# fpga_config.net
KiCad netlist of a schematic drawn in Altium Designer
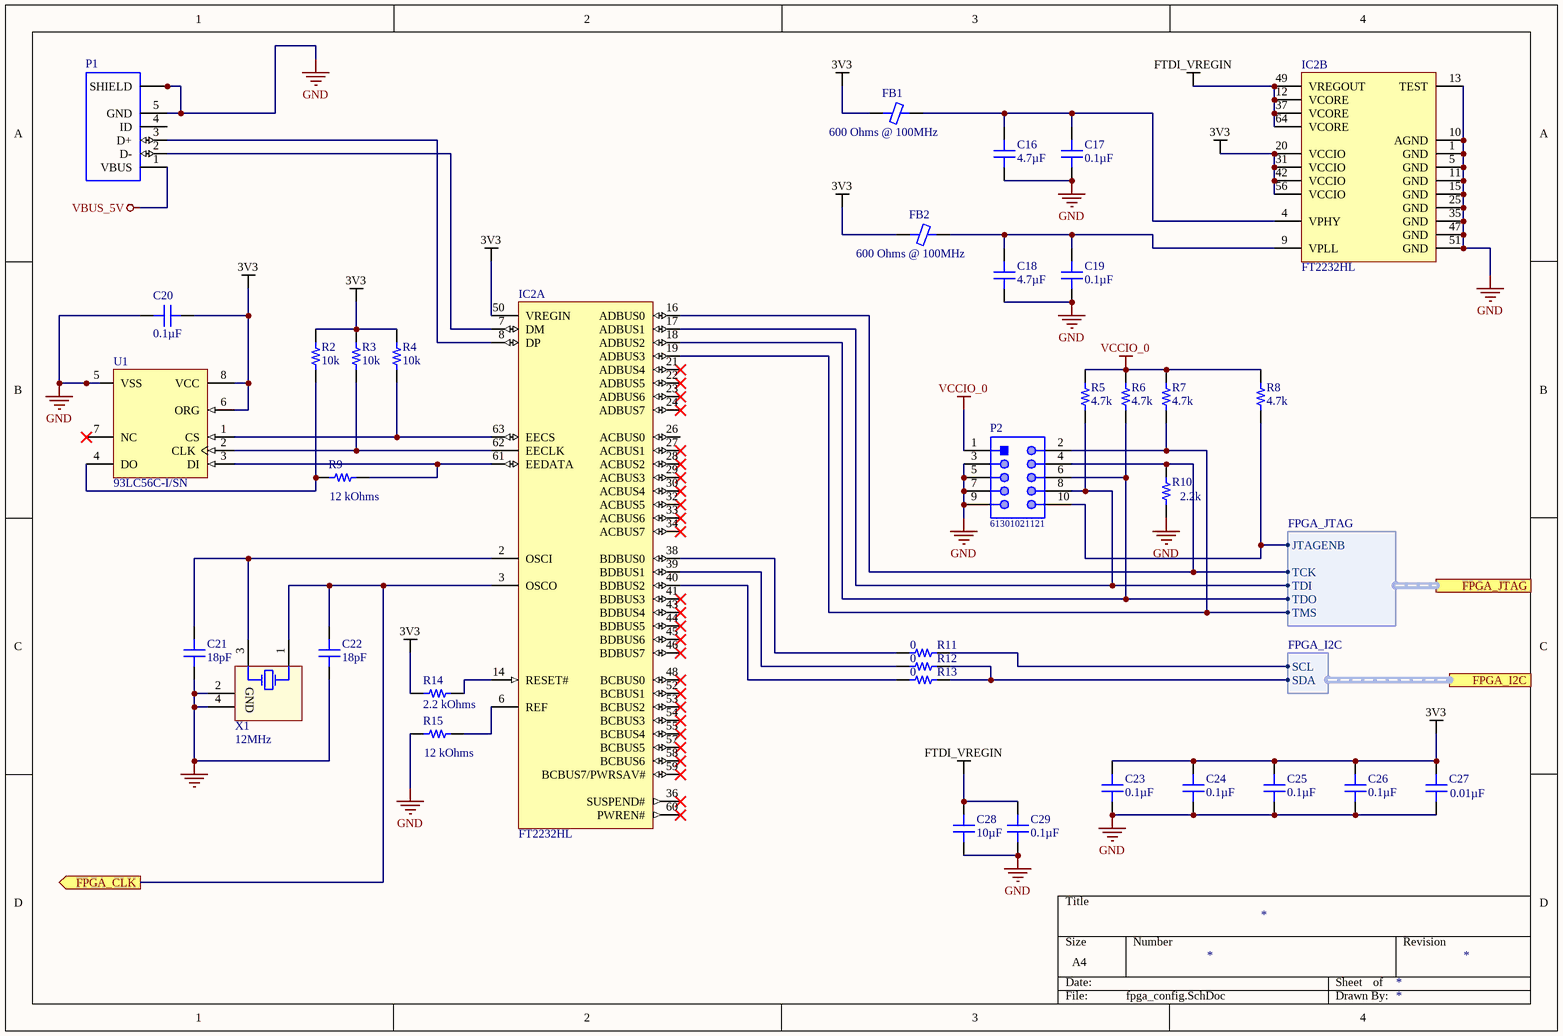
[diagram p0: fpga_config.SchDoc]

(export (version "E")
  (design (tool "Eeschema 10.0.6"))
  (components
    (comp (ref "C16")
      (value "4.7µF")
      (footprint "CAP 0603_1608")
      (description "CAP CER 4.7UF 10V X5R 0603")
      (fields (field (name "PART NUMBER") "LMK107BJ475KA-T") (field (name "MANUFACTURER") "Taiyo Yuden"))
      (libsource (lib "Celestial Altium Library - altium_library (2)") (part "Capacitor"))
    )
    (comp (ref "C17")
      (value "0.1µF")
      (footprint "CAP 0603_1608")
      (description "CAP CER 0.1UF 50V X7R 0603")
      (fields (field (name "PART NUMBER") "C0603C104K5RAC7411") (field (name "MANUFACTURER") "KEMET"))
      (libsource (lib "Celestial Altium Library - altium_library (2)") (part "Capacitor"))
    )
    (comp (ref "C18")
      (value "4.7µF")
      (footprint "CAP 0603_1608")
      (description "CAP CER 4.7UF 10V X5R 0603")
      (fields (field (name "PART NUMBER") "LMK107BJ475KA-T") (field (name "MANUFACTURER") "Taiyo Yuden"))
      (libsource (lib "Celestial Altium Library - altium_library (2)") (part "Capacitor"))
    )
    (comp (ref "C19")
      (value "0.1µF")
      (footprint "CAP 0603_1608")
      (description "CAP CER 0.1UF 50V X7R 0603")
      (fields (field (name "PART NUMBER") "C0603C104K5RAC7411") (field (name "MANUFACTURER") "KEMET"))
      (libsource (lib "Celestial Altium Library - altium_library (2)") (part "Capacitor"))
    )
    (comp (ref "C20")
      (value "0.1µF")
      (footprint "CAP 0603_1608")
      (description "CAP CER 0.1UF 50V X7R 0603")
      (fields (field (name "PART NUMBER") "C0603C104K5RAC7411") (field (name "MANUFACTURER") "KEMET"))
      (libsource (lib "Celestial Altium Library - altium_library (2)") (part "Capacitor"))
    )
    (comp (ref "C21")
      (value "18pF")
      (footprint "CAP 0603_1608")
      (description "CAP CER 18PF 10V C0G/NP0 0603")
      (fields
        (field (name "PART NUMBER") "VJ0603A180FXQCW1BC")
        (field (name "MANUFACTURER") "Vishay Vitramon")
      )
      (libsource (lib "Celestial Altium Library - altium_library (2)") (part "Capacitor"))
    )
    (comp (ref "C22")
      (value "18pF")
      (footprint "CAP 0603_1608")
      (description "CAP CER 18PF 10V C0G/NP0 0603")
      (fields
        (field (name "PART NUMBER") "VJ0603A180FXQCW1BC")
        (field (name "MANUFACTURER") "Vishay Vitramon")
      )
      (libsource (lib "Celestial Altium Library - altium_library (2)") (part "Capacitor"))
    )
    (comp (ref "C23")
      (value "0.1µF")
      (footprint "CAP 0603_1608")
      (description "CAP CER 0.1UF 50V X7R 0603")
      (fields (field (name "PART NUMBER") "C0603C104K5RAC7411") (field (name "MANUFACTURER") "KEMET"))
      (libsource (lib "Celestial Altium Library - altium_library (2)") (part "Capacitor"))
    )
    (comp (ref "C24")
      (value "0.1µF")
      (footprint "CAP 0603_1608")
      (description "CAP CER 0.1UF 50V X7R 0603")
      (fields (field (name "PART NUMBER") "C0603C104K5RAC7411") (field (name "MANUFACTURER") "KEMET"))
      (libsource (lib "Celestial Altium Library - altium_library (2)") (part "Capacitor"))
    )
    (comp (ref "C25")
      (value "0.1µF")
      (footprint "CAP 0603_1608")
      (description "CAP CER 0.1UF 50V X7R 0603")
      (fields (field (name "PART NUMBER") "C0603C104K5RAC7411") (field (name "MANUFACTURER") "KEMET"))
      (libsource (lib "Celestial Altium Library - altium_library (2)") (part "Capacitor"))
    )
    (comp (ref "C26")
      (value "0.1µF")
      (footprint "CAP 0603_1608")
      (description "CAP CER 0.1UF 50V X7R 0603")
      (fields (field (name "PART NUMBER") "C0603C104K5RAC7411") (field (name "MANUFACTURER") "KEMET"))
      (libsource (lib "Celestial Altium Library - altium_library (2)") (part "Capacitor"))
    )
    (comp (ref "C27")
      (value "0.01µF")
      (footprint "CAP 0603_1608")
      (description "CAP CER 0.01UF 250V X7R 0603")
      (fields (field (name "PART NUMBER") "C0603C103KARACAUTO") (field (name "MANUFACTURER") "KEMET"))
      (libsource (lib "Celestial Altium Library - altium_library (2)") (part "Capacitor"))
    )
    (comp (ref "C28")
      (value "10µF")
      (footprint "CAP 0603_1608")
      (description "CAP CER 10UF 6.3V X5R 0603")
      (fields
        (field (name "PART NUMBER") "GRM188R60J106ME47D")
        (field (name "MANUFACTURER") "Murata Electronics")
      )
      (libsource (lib "Celestial Altium Library - altium_library (2)") (part "Capacitor"))
    )
    (comp (ref "C29")
      (value "0.1µF")
      (footprint "CAP 0603_1608")
      (description "CAP CER 0.1UF 50V X7R 0603")
      (fields (field (name "PART NUMBER") "C0603C104K5RAC7411") (field (name "MANUFACTURER") "KEMET"))
      (libsource (lib "Celestial Altium Library - altium_library (2)") (part "Capacitor"))
    )
    (comp (ref "FB1")
      (value "600 Ohms @ 100MHz")
      (footprint "FER 0603_1608")
      (description "FERRITE BEAD 600 OHM 0603 1LN")
      (fields
        (field (name "PART NUMBER") "BLM18AG601SN1D")
        (field (name "MANUFACTURER") "Murata Electronics")
      )
      (libsource (lib "Celestial Altium Library - altium_library (2)") (part "Ferrite Chip"))
    )
    (comp (ref "FB2")
      (value "600 Ohms @ 100MHz")
      (footprint "FER 0603_1608")
      (description "FERRITE BEAD 600 OHM 0603 1LN")
      (fields
        (field (name "PART NUMBER") "BLM18AG601SN1D")
        (field (name "MANUFACTURER") "Murata Electronics")
      )
      (libsource (lib "Celestial Altium Library - altium_library (2)") (part "Ferrite Chip"))
    )
    (comp (ref "IC2")
      (value "FT2232HL")
      (footprint "FTDI-LQFP-64_L")
      (fields (field (name "MANUFACTURER") "FTDI"))
      (libsource (lib "Altium Content Vault") (part "FTDI-FT2232HL-LQFP-64"))
    )
    (comp (ref "P1")
      (value "47346-0001")
      (footprint "MOLEX_47346-0001")
      (description "CONN RCPT 5POS MICRO USB R/A  SMD")
      (libsource (lib "47346-0001") (part "47346-0001"))
    )
    (comp (ref "P2")
      (value "61301021121")
      (footprint "61301021121")
      (description "THT Vertical Pin Header WR-PHD, Pitch 2.54 mm, Dual Row, 10 pins")
      (fields (field (name "MANUFACTURER") "Wurth Elektronik") (field (name "PUBLISHER") "WurthElektronik"))
      (libsource (lib "Altium Content Vault") (part "WE-CN-2P-M-R10"))
    )
    (comp (ref "R2")
      (value "10k")
      (footprint "RES 0603_1608")
      (description "RES 10K OHM 0.1% 1/16W 0603")
      (fields
        (field (name "PART NUMBER") "RNCS0603BKE10K0")
        (field (name "MANUFACTURER") "Stackpole Electronics Inc")
      )
      (libsource (lib "Celestial Altium Library - altium_library (2)") (part "Resistor"))
    )
    (comp (ref "R3")
      (value "10k")
      (footprint "RES 0603_1608")
      (description "RES 10K OHM 0.1% 1/16W 0603")
      (fields
        (field (name "PART NUMBER") "RNCS0603BKE10K0")
        (field (name "MANUFACTURER") "Stackpole Electronics Inc")
      )
      (libsource (lib "Celestial Altium Library - altium_library (2)") (part "Resistor"))
    )
    (comp (ref "R4")
      (value "10k")
      (footprint "RES 0603_1608")
      (description "RES 10K OHM 0.1% 1/16W 0603")
      (fields
        (field (name "PART NUMBER") "RNCS0603BKE10K0")
        (field (name "MANUFACTURER") "Stackpole Electronics Inc")
      )
      (libsource (lib "Celestial Altium Library - altium_library (2)") (part "Resistor"))
    )
    (comp (ref "R5")
      (value "4.7k")
      (footprint "RES 0603_1608")
      (description "RES SMD 4.7K OHM 1% 1/10W 0603")
      (fields (field (name "PART NUMBER") "RT0603FRE074K7L") (field (name "MANUFACTURER") "Yageo"))
      (libsource (lib "Celestial Altium Library - altium_library (2)") (part "Resistor"))
    )
    (comp (ref "R6")
      (value "4.7k")
      (footprint "RES 0603_1608")
      (description "RES SMD 4.7K OHM 1% 1/10W 0603")
      (fields (field (name "PART NUMBER") "RT0603FRE074K7L") (field (name "MANUFACTURER") "Yageo"))
      (libsource (lib "Celestial Altium Library - altium_library (2)") (part "Resistor"))
    )
    (comp (ref "R7")
      (value "4.7k")
      (footprint "RES 0603_1608")
      (description "RES SMD 4.7K OHM 1% 1/10W 0603")
      (fields (field (name "PART NUMBER") "RT0603FRE074K7L") (field (name "MANUFACTURER") "Yageo"))
      (libsource (lib "Celestial Altium Library - altium_library (2)") (part "Resistor"))
    )
    (comp (ref "R8")
      (value "4.7k")
      (footprint "RES 0603_1608")
      (description "RES SMD 4.7K OHM 1% 1/10W 0603")
      (fields (field (name "PART NUMBER") "RT0603FRE074K7L") (field (name "MANUFACTURER") "Yageo"))
      (libsource (lib "Celestial Altium Library - altium_library (2)") (part "Resistor"))
    )
    (comp (ref "R9")
      (value "12 kOhms")
      (footprint "RES 0603_1608")
      (description "RES 12K OHM 5% 1/10W 0603")
      (fields
        (field (name "PART NUMBER") "RMCF0603JT12K0")
        (field (name "MANUFACTURER") "Stackpole Electronics Inc")
      )
      (libsource (lib "Celestial Altium Library - altium_library (2)") (part "Resistor"))
    )
    (comp (ref "R10")
      (value "2.2k")
      (footprint "RES 0603_1608")
      (description "RES SMD 2.2K OHM 0.1% 1/10W 0603")
      (fields
        (field (name "PART NUMBER") "ERA-3AEB222V")
        (field (name "MANUFACTURER") "Panasonic Electronic Components")
      )
      (libsource (lib "Celestial Altium Library - altium_library (2)") (part "Resistor"))
    )
    (comp (ref "R11")
      (value "0")
      (footprint "RES 0603_1608")
      (description "RES 0 OHM JUMPER 0603")
      (fields
        (field (name "PART NUMBER") "TLRZ1JTTD")
        (field (name "MANUFACTURER") "KOA Speer Electronics, Inc.")
      )
      (libsource (lib "Celestial Altium Library - altium_library (2)") (part "Resistor"))
    )
    (comp (ref "R12")
      (value "0")
      (footprint "RES 0603_1608")
      (description "RES 0 OHM JUMPER 0603")
      (fields
        (field (name "PART NUMBER") "TLRZ1JTTD")
        (field (name "MANUFACTURER") "KOA Speer Electronics, Inc.")
      )
      (libsource (lib "Celestial Altium Library - altium_library (2)") (part "Resistor"))
    )
    (comp (ref "R13")
      (value "0")
      (footprint "RES 0603_1608")
      (description "RES 0 OHM JUMPER 0603")
      (fields
        (field (name "PART NUMBER") "TLRZ1JTTD")
        (field (name "MANUFACTURER") "KOA Speer Electronics, Inc.")
      )
      (libsource (lib "Celestial Altium Library - altium_library (2)") (part "Resistor"))
    )
    (comp (ref "R14")
      (value "2.2 kOhms")
      (footprint "RES 0603_1608")
      (description "RES SMD 2.2K OHM 0.1% 1/10W 0603")
      (fields
        (field (name "PART NUMBER") "ERA-3AEB222V")
        (field (name "MANUFACTURER") "Panasonic Electronic Components")
      )
      (libsource (lib "Celestial Altium Library - altium_library (2)") (part "Resistor"))
    )
    (comp (ref "R15")
      (value "12 kOhms")
      (footprint "RES 0603_1608")
      (description "RES 12K OHM 5% 1/10W 0603")
      (fields
        (field (name "PART NUMBER") "RMCF0603JT12K0")
        (field (name "MANUFACTURER") "Stackpole Electronics Inc")
      )
      (libsource (lib "Celestial Altium Library - altium_library (2)") (part "Resistor"))
    )
    (comp (ref "U1")
      (value "93LC56C-I/SN")
      (footprint "SOIC-SN8_L")
      (description "2K, 256x8 or 128x16-bit, 2.5V Microwire Serial EEPROM, 8-Pin SOIC 150mil, Industrial Temperature")
      (libsource (lib "Altium Content Vault") (part "MEM-SEEPROM-93AA46C-P-8"))
    )
    (comp (ref "X1")
      (value "12MHz")
      (footprint "ABRA-ABMM2-4_V")
      (fields (field (name "MANUFACTURER") "Abracon") (field (name "PARTNUMBER") "ABMM2-8.000MHZ-E2-T"))
      (libsource (lib "Altium Content Vault") (part "ABRA-XTAL_1-3-4"))
    )
  )
  (nets
    (net (code "3") (name "/FPGA_CLK") (class "Default")
      (node (ref "C22") (pin "2") (pinfunction "2_2") (pintype "passive"))
      (node (ref "IC2") (pin "3") (pinfunction "OSCO_3") (pintype "passive"))
      (node (ref "X1") (pin "1") (pinfunction "X1_1") (pintype "passive"))
    )
    (net (code "4") (name "/JTAGENB") (class "Default")
      (node (ref "P2") (pin "10") (pinfunction "10_10") (pintype "passive"))
      (node (ref "R8") (pin "1") (pinfunction "1_1") (pintype "passive"))
    )
    (net (code "5") (name "/SCL") (class "Default")
      (node (ref "R11") (pin "2") (pinfunction "2_2") (pintype "passive"))
    )
    (net (code "6") (name "/SDA") (class "Default")
      (node (ref "R12") (pin "2") (pinfunction "2_2") (pintype "passive"))
      (node (ref "R13") (pin "2") (pinfunction "2_2") (pintype "passive"))
    )
    (net (code "7") (name "/TCK") (class "Default")
      (node (ref "IC2") (pin "16") (pinfunction "ADBUS0_16") (pintype "bidirectional"))
      (node (ref "P2") (pin "4") (pinfunction "4_4") (pintype "passive"))
      (node (ref "R10") (pin "2") (pinfunction "2_2") (pintype "passive"))
    )
    (net (code "8") (name "/TDI") (class "Default")
      (node (ref "IC2") (pin "17") (pinfunction "ADBUS1_17") (pintype "bidirectional"))
      (node (ref "P2") (pin "8") (pinfunction "8_8") (pintype "passive"))
      (node (ref "R5") (pin "1") (pinfunction "1_1") (pintype "passive"))
    )
    (net (code "9") (name "/TDO") (class "Default")
      (node (ref "IC2") (pin "18") (pinfunction "ADBUS2_18") (pintype "bidirectional"))
      (node (ref "P2") (pin "6") (pinfunction "6_6") (pintype "passive"))
      (node (ref "R6") (pin "1") (pinfunction "1_1") (pintype "passive"))
    )
    (net (code "10") (name "/TMS") (class "Default")
      (node (ref "IC2") (pin "19") (pinfunction "ADBUS3_19") (pintype "bidirectional"))
      (node (ref "P2") (pin "2") (pinfunction "2_2") (pintype "passive"))
      (node (ref "R7") (pin "1") (pinfunction "1_1") (pintype "passive"))
    )
    (net (code "13") (name "3V3") (class "Default")
      (node (ref "C20") (pin "1") (pinfunction "1_1") (pintype "passive"))
      (node (ref "C23") (pin "2") (pinfunction "2_2") (pintype "passive"))
      (node (ref "C24") (pin "2") (pinfunction "2_2") (pintype "passive"))
      (node (ref "C25") (pin "2") (pinfunction "2_2") (pintype "passive"))
      (node (ref "C26") (pin "2") (pinfunction "2_2") (pintype "passive"))
      (node (ref "C27") (pin "2") (pinfunction "2_2") (pintype "passive"))
      (node (ref "FB1") (pin "1") (pinfunction "1_1") (pintype "passive"))
      (node (ref "FB2") (pin "1") (pinfunction "1_1") (pintype "passive"))
      (node (ref "IC2") (pin "20") (pinfunction "VCCIO_20") (pintype "power_in"))
      (node (ref "IC2") (pin "31") (pinfunction "VCCIO_31") (pintype "power_in"))
      (node (ref "IC2") (pin "42") (pinfunction "VCCIO_42") (pintype "power_in"))
      (node (ref "IC2") (pin "50") (pinfunction "VREGIN_50") (pintype "power_in"))
      (node (ref "IC2") (pin "56") (pinfunction "VCCIO_56") (pintype "power_in"))
      (node (ref "R14") (pin "1") (pinfunction "1_1") (pintype "passive"))
      (node (ref "R2") (pin "2") (pinfunction "2_2") (pintype "passive"))
      (node (ref "R3") (pin "2") (pinfunction "2_2") (pintype "passive"))
      (node (ref "R4") (pin "2") (pinfunction "2_2") (pintype "passive"))
      (node (ref "U1") (pin "6") (pinfunction "ORG_6") (pintype "input"))
      (node (ref "U1") (pin "8") (pinfunction "VCC_8") (pintype "power_in"))
    )
    (net (code "14") (name "FTDI_VREGIN") (class "Default")
      (node (ref "C28") (pin "2") (pinfunction "2_2") (pintype "passive"))
      (node (ref "C29") (pin "2") (pinfunction "2_2") (pintype "passive"))
      (node (ref "IC2") (pin "12") (pinfunction "VCORE_12") (pintype "power_in"))
      (node (ref "IC2") (pin "37") (pinfunction "VCORE_37") (pintype "power_in"))
      (node (ref "IC2") (pin "49") (pinfunction "VREGOUT_49") (pintype "power_in"))
      (node (ref "IC2") (pin "64") (pinfunction "VCORE_64") (pintype "power_in"))
    )
    (net (code "15") (name "GND") (class "Default")
      (node (ref "C16") (pin "1") (pinfunction "1_1") (pintype "passive"))
      (node (ref "C17") (pin "1") (pinfunction "1_1") (pintype "passive"))
      (node (ref "C18") (pin "1") (pinfunction "1_1") (pintype "passive"))
      (node (ref "C19") (pin "1") (pinfunction "1_1") (pintype "passive"))
      (node (ref "C20") (pin "2") (pinfunction "2_2") (pintype "passive"))
      (node (ref "C21") (pin "1") (pinfunction "1_1") (pintype "passive"))
      (node (ref "C22") (pin "1") (pinfunction "1_1") (pintype "passive"))
      (node (ref "C23") (pin "1") (pinfunction "1_1") (pintype "passive"))
      (node (ref "C24") (pin "1") (pinfunction "1_1") (pintype "passive"))
      (node (ref "C25") (pin "1") (pinfunction "1_1") (pintype "passive"))
      (node (ref "C26") (pin "1") (pinfunction "1_1") (pintype "passive"))
      (node (ref "C27") (pin "1") (pinfunction "1_1") (pintype "passive"))
      (node (ref "C28") (pin "1") (pinfunction "1_1") (pintype "passive"))
      (node (ref "C29") (pin "1") (pinfunction "1_1") (pintype "passive"))
      (node (ref "IC2") (pin "1") (pinfunction "GND_1") (pintype "power_in"))
      (node (ref "IC2") (pin "10") (pinfunction "AGND_10") (pintype "power_in"))
      (node (ref "IC2") (pin "11") (pinfunction "GND_11") (pintype "power_in"))
      (node (ref "IC2") (pin "13") (pinfunction "TEST_13") (pintype "passive"))
      (node (ref "IC2") (pin "15") (pinfunction "GND_15") (pintype "power_in"))
      (node (ref "IC2") (pin "25") (pinfunction "GND_25") (pintype "power_in"))
      (node (ref "IC2") (pin "35") (pinfunction "GND_35") (pintype "power_in"))
      (node (ref "IC2") (pin "47") (pinfunction "GND_47") (pintype "power_in"))
      (node (ref "IC2") (pin "5") (pinfunction "GND_5") (pintype "power_in"))
      (node (ref "IC2") (pin "51") (pinfunction "GND_51") (pintype "power_in"))
      (node (ref "P1") (pin "5") (pinfunction "GND_5") (pintype "power_in"))
      (node (ref "P1") (pin "SH1") (pinfunction "SHIELD_SH1") (pintype "passive"))
      (node (ref "P1") (pin "SH2") (pinfunction "SHIELD_SH2") (pintype "passive"))
      (node (ref "P1") (pin "SH3") (pinfunction "SHIELD_SH3") (pintype "passive"))
      (node (ref "P1") (pin "SH4") (pinfunction "SHIELD_SH4") (pintype "passive"))
      (node (ref "P1") (pin "SH5") (pinfunction "SHIELD_SH5") (pintype "passive"))
      (node (ref "P1") (pin "SH6") (pinfunction "SHIELD_SH6") (pintype "passive"))
      (node (ref "P2") (pin "3") (pinfunction "3_3") (pintype "passive"))
      (node (ref "P2") (pin "5") (pinfunction "5_5") (pintype "passive"))
      (node (ref "P2") (pin "7") (pinfunction "7_7") (pintype "passive"))
      (node (ref "P2") (pin "9") (pinfunction "9_9") (pintype "passive"))
      (node (ref "R10") (pin "1") (pinfunction "1_1") (pintype "passive"))
      (node (ref "R15") (pin "1") (pinfunction "1_1") (pintype "passive"))
      (node (ref "U1") (pin "5") (pinfunction "VSS_5") (pintype "power_in"))
      (node (ref "X1") (pin "2") (pinfunction "GND_2") (pintype "power_in"))
      (node (ref "X1") (pin "4") (pinfunction "GND_4") (pintype "power_in"))
    )
    (net (code "16") (name "Net-(IC2A-BDBUS0)") (class "Default")
      (node (ref "IC2") (pin "38") (pinfunction "BDBUS0_38") (pintype "bidirectional"))
      (node (ref "R11") (pin "1") (pinfunction "1_1") (pintype "passive"))
    )
    (net (code "17") (name "Net-(IC2A-BDBUS1)") (class "Default")
      (node (ref "IC2") (pin "39") (pinfunction "BDBUS1_39") (pintype "bidirectional"))
      (node (ref "R12") (pin "1") (pinfunction "1_1") (pintype "passive"))
    )
    (net (code "18") (name "Net-(IC2A-BDBUS2)") (class "Default")
      (node (ref "IC2") (pin "40") (pinfunction "BDBUS2_40") (pintype "bidirectional"))
      (node (ref "R13") (pin "1") (pinfunction "1_1") (pintype "passive"))
    )
    (net (code "19") (name "Net-(IC2A-DM)") (class "Default")
      (node (ref "IC2") (pin "7") (pinfunction "DM_7") (pintype "bidirectional"))
      (node (ref "P1") (pin "2") (pinfunction "D-_2") (pintype "bidirectional"))
    )
    (net (code "20") (name "Net-(IC2A-DP)") (class "Default")
      (node (ref "IC2") (pin "8") (pinfunction "DP_8") (pintype "bidirectional"))
      (node (ref "P1") (pin "3") (pinfunction "D+_3") (pintype "bidirectional"))
    )
    (net (code "21") (name "Net-(IC2A-EECLK)") (class "Default")
      (node (ref "IC2") (pin "62") (pinfunction "EECLK_62") (pintype "tri_state"))
      (node (ref "R3") (pin "1") (pinfunction "1_1") (pintype "passive"))
      (node (ref "U1") (pin "2") (pinfunction "CLK_2") (pintype "input"))
    )
    (net (code "22") (name "Net-(IC2A-EECS)") (class "Default")
      (node (ref "IC2") (pin "63") (pinfunction "EECS_63") (pintype "bidirectional"))
      (node (ref "R4") (pin "1") (pinfunction "1_1") (pintype "passive"))
      (node (ref "U1") (pin "1") (pinfunction "CS_1") (pintype "input"))
    )
    (net (code "23") (name "Net-(IC2A-EEDATA)") (class "Default")
      (node (ref "IC2") (pin "61") (pinfunction "EEDATA_61") (pintype "bidirectional"))
      (node (ref "R9") (pin "2") (pinfunction "2_2") (pintype "passive"))
      (node (ref "U1") (pin "3") (pinfunction "DI_3") (pintype "input"))
    )
    (net (code "24") (name "Net-(IC2A-OSCI)") (class "Default")
      (node (ref "C21") (pin "2") (pinfunction "2_2") (pintype "passive"))
      (node (ref "IC2") (pin "2") (pinfunction "OSCI_2") (pintype "passive"))
      (node (ref "X1") (pin "3") (pinfunction "X2_3") (pintype "passive"))
    )
    (net (code "25") (name "Net-(IC2A-REF)") (class "Default")
      (node (ref "IC2") (pin "6") (pinfunction "REF_6") (pintype "passive"))
      (node (ref "R15") (pin "2") (pinfunction "2_2") (pintype "passive"))
    )
    (net (code "26") (name "Net-(IC2A-RESET#)") (class "Default")
      (node (ref "IC2") (pin "14") (pinfunction "RESET#_14") (pintype "input"))
      (node (ref "R14") (pin "2") (pinfunction "2_2") (pintype "passive"))
    )
    (net (code "27") (name "Net-(IC2B-VPHY)") (class "Default")
      (node (ref "C16") (pin "2") (pinfunction "2_2") (pintype "passive"))
      (node (ref "C17") (pin "2") (pinfunction "2_2") (pintype "passive"))
      (node (ref "FB1") (pin "2") (pinfunction "2_2") (pintype "passive"))
      (node (ref "IC2") (pin "4") (pinfunction "VPHY_4") (pintype "power_in"))
    )
    (net (code "28") (name "Net-(IC2B-VPLL)") (class "Default")
      (node (ref "C18") (pin "2") (pinfunction "2_2") (pintype "passive"))
      (node (ref "C19") (pin "2") (pinfunction "2_2") (pintype "passive"))
      (node (ref "FB2") (pin "2") (pinfunction "2_2") (pintype "passive"))
      (node (ref "IC2") (pin "9") (pinfunction "VPLL_9") (pintype "power_in"))
    )
    (net (code "29") (name "Net-(U1-DO)") (class "Default")
      (node (ref "R2") (pin "1") (pinfunction "1_1") (pintype "passive"))
      (node (ref "R9") (pin "1") (pinfunction "1_1") (pintype "passive"))
      (node (ref "U1") (pin "4") (pinfunction "DO_4") (pintype "tri_state"))
    )
    (net (code "30") (name "VBUS_5V") (class "Default")
      (node (ref "P1") (pin "1") (pinfunction "VBUS_1") (pintype "power_in"))
    )
    (net (code "31") (name "VCCIO_0") (class "Default")
      (node (ref "P2") (pin "1") (pinfunction "1_1") (pintype "passive"))
      (node (ref "R5") (pin "2") (pinfunction "2_2") (pintype "passive"))
      (node (ref "R6") (pin "2") (pinfunction "2_2") (pintype "passive"))
      (node (ref "R7") (pin "2") (pinfunction "2_2") (pintype "passive"))
      (node (ref "R8") (pin "2") (pinfunction "2_2") (pintype "passive"))
    )
    (net (code "32") (name "unconnected-(IC2A-ACBUS0-Pad26)") (class "Default")
      (node (ref "IC2") (pin "26") (pinfunction "ACBUS0_26") (pintype "bidirectional"))
    )
    (net (code "33") (name "unconnected-(IC2A-ACBUS1-Pad27)") (class "Default")
      (node (ref "IC2") (pin "27") (pinfunction "ACBUS1_27") (pintype "bidirectional+no_connect"))
    )
    (net (code "34") (name "unconnected-(IC2A-ACBUS2-Pad28)") (class "Default")
      (node (ref "IC2") (pin "28") (pinfunction "ACBUS2_28") (pintype "bidirectional+no_connect"))
    )
    (net (code "35") (name "unconnected-(IC2A-ACBUS3-Pad29)") (class "Default")
      (node (ref "IC2") (pin "29") (pinfunction "ACBUS3_29") (pintype "bidirectional+no_connect"))
    )
    (net (code "36") (name "unconnected-(IC2A-ACBUS4-Pad30)") (class "Default")
      (node (ref "IC2") (pin "30") (pinfunction "ACBUS4_30") (pintype "bidirectional+no_connect"))
    )
    (net (code "37") (name "unconnected-(IC2A-ACBUS5-Pad32)") (class "Default")
      (node (ref "IC2") (pin "32") (pinfunction "ACBUS5_32") (pintype "bidirectional+no_connect"))
    )
    (net (code "38") (name "unconnected-(IC2A-ACBUS6-Pad33)") (class "Default")
      (node (ref "IC2") (pin "33") (pinfunction "ACBUS6_33") (pintype "bidirectional+no_connect"))
    )
    (net (code "39") (name "unconnected-(IC2A-ACBUS7-Pad34)") (class "Default")
      (node (ref "IC2") (pin "34") (pinfunction "ACBUS7_34") (pintype "bidirectional+no_connect"))
    )
    (net (code "40") (name "unconnected-(IC2A-ADBUS4-Pad21)") (class "Default")
      (node (ref "IC2") (pin "21") (pinfunction "ADBUS4_21") (pintype "bidirectional+no_connect"))
    )
    (net (code "41") (name "unconnected-(IC2A-ADBUS5-Pad22)") (class "Default")
      (node (ref "IC2") (pin "22") (pinfunction "ADBUS5_22") (pintype "bidirectional+no_connect"))
    )
    (net (code "42") (name "unconnected-(IC2A-ADBUS6-Pad23)") (class "Default")
      (node (ref "IC2") (pin "23") (pinfunction "ADBUS6_23") (pintype "bidirectional+no_connect"))
    )
    (net (code "43") (name "unconnected-(IC2A-ADBUS7-Pad24)") (class "Default")
      (node (ref "IC2") (pin "24") (pinfunction "ADBUS7_24") (pintype "bidirectional+no_connect"))
    )
    (net (code "44") (name "unconnected-(IC2A-BCBUS0-Pad48)") (class "Default")
      (node (ref "IC2") (pin "48") (pinfunction "BCBUS0_48") (pintype "bidirectional+no_connect"))
    )
    (net (code "45") (name "unconnected-(IC2A-BCBUS1-Pad52)") (class "Default")
      (node (ref "IC2") (pin "52") (pinfunction "BCBUS1_52") (pintype "bidirectional+no_connect"))
    )
    (net (code "46") (name "unconnected-(IC2A-BCBUS2-Pad53)") (class "Default")
      (node (ref "IC2") (pin "53") (pinfunction "BCBUS2_53") (pintype "bidirectional+no_connect"))
    )
    (net (code "47") (name "unconnected-(IC2A-BCBUS3-Pad54)") (class "Default")
      (node (ref "IC2") (pin "54") (pinfunction "BCBUS3_54") (pintype "bidirectional+no_connect"))
    )
    (net (code "48") (name "unconnected-(IC2A-BCBUS4-Pad55)") (class "Default")
      (node (ref "IC2") (pin "55") (pinfunction "BCBUS4_55") (pintype "bidirectional+no_connect"))
    )
    (net (code "49") (name "unconnected-(IC2A-BCBUS5-Pad57)") (class "Default")
      (node (ref "IC2") (pin "57") (pinfunction "BCBUS5_57") (pintype "bidirectional+no_connect"))
    )
    (net (code "50") (name "unconnected-(IC2A-BCBUS6-Pad58)") (class "Default")
      (node (ref "IC2") (pin "58") (pinfunction "BCBUS6_58") (pintype "bidirectional+no_connect"))
    )
    (net (code "51") (name "unconnected-(IC2A-BCBUS7{slash}PWRSAV#-Pad59)") (class "Default")
      (node (ref "IC2") (pin "59") (pinfunction "BCBUS7/PWRSAV#_59") (pintype "bidirectional+no_connect"))
    )
    (net (code "52") (name "unconnected-(IC2A-BDBUS3-Pad41)") (class "Default")
      (node (ref "IC2") (pin "41") (pinfunction "BDBUS3_41") (pintype "bidirectional+no_connect"))
    )
    (net (code "53") (name "unconnected-(IC2A-BDBUS4-Pad43)") (class "Default")
      (node (ref "IC2") (pin "43") (pinfunction "BDBUS4_43") (pintype "bidirectional+no_connect"))
    )
    (net (code "54") (name "unconnected-(IC2A-BDBUS5-Pad44)") (class "Default")
      (node (ref "IC2") (pin "44") (pinfunction "BDBUS5_44") (pintype "bidirectional+no_connect"))
    )
    (net (code "55") (name "unconnected-(IC2A-BDBUS6-Pad45)") (class "Default")
      (node (ref "IC2") (pin "45") (pinfunction "BDBUS6_45") (pintype "bidirectional+no_connect"))
    )
    (net (code "56") (name "unconnected-(IC2A-BDBUS7-Pad46)") (class "Default")
      (node (ref "IC2") (pin "46") (pinfunction "BDBUS7_46") (pintype "bidirectional+no_connect"))
    )
    (net (code "57") (name "unconnected-(IC2A-PWREN#-Pad60)") (class "Default")
      (node (ref "IC2") (pin "60") (pinfunction "PWREN#_60") (pintype "output+no_connect"))
    )
    (net (code "58") (name "unconnected-(IC2A-SUSPEND#-Pad36)") (class "Default")
      (node (ref "IC2") (pin "36") (pinfunction "SUSPEND#_36") (pintype "output+no_connect"))
    )
    (net (code "59") (name "unconnected-(P1-ID-Pad4)") (class "Default")
      (node (ref "P1") (pin "4") (pinfunction "ID_4") (pintype "passive"))
    )
    (net (code "60") (name "unconnected-(U1-NC-Pad7)") (class "Default")
      (node (ref "U1") (pin "7") (pinfunction "NC_7") (pintype "passive+no_connect"))
    )
  )
)
